# NBM.net
KiCad netlist of a schematic drawn in Altium Designer
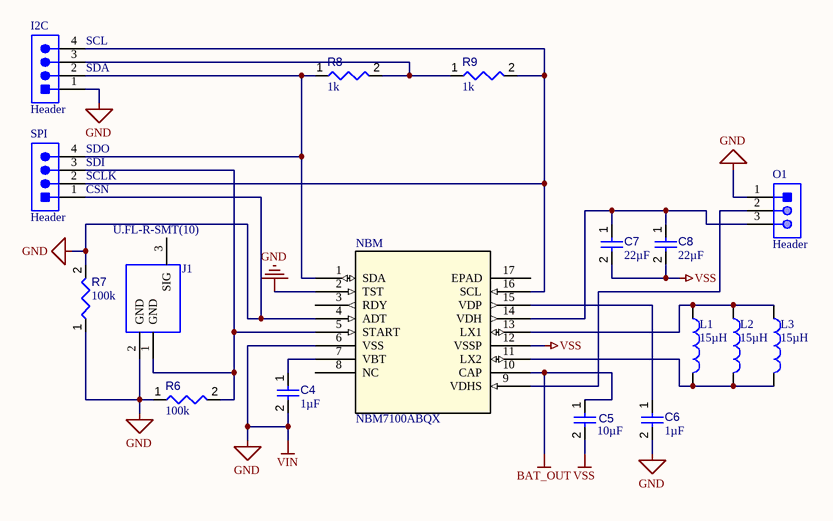
[diagram p0: NBM.SchDoc]

(export (version "E")
  (design (tool "Eeschema 10.0.6"))
  (components
    (comp (ref "C4")
      (value "1µF")
      (footprint "FP-GRM155-0_1-IPC_C")
      (fields (field (name "Comment") "GRM155Z71A105KE01D"))
      (libsource (lib "21520293 21520293") (part "CAP-NP-2"))
    )
    (comp (ref "C5")
      (value "10µF")
      (footprint "FP-GRM155-0_2-IPC_A")
      (fields (field (name "Comment") "GRM155R60J106ME44D"))
      (libsource (lib "21520293 21520293") (part "CAP-NP-2"))
    )
    (comp (ref "C6")
      (value "1µF")
      (footprint "FP-GRM155-0_1-IPC_C")
      (fields (field (name "Comment") "GRM155Z71A105KE01D"))
      (libsource (lib "21520293 21520293") (part "CAP-NP-2"))
    )
    (comp (ref "C7")
      (value "22µF")
      (footprint "FP-GRM158-0_2-MFG")
      (fields (field (name "Comment") "GRM158R61A226ME15D"))
      (libsource (lib "21520293 21520293") (part "CAP-NP-2"))
    )
    (comp (ref "C8")
      (value "22µF")
      (footprint "FP-GRM158-0_2-MFG")
      (fields (field (name "Comment") "GRM158R61A226ME15D"))
      (libsource (lib "21520293 21520293") (part "CAP-NP-2"))
    )
    (comp (ref "I2C")
      (value "Header")
      (footprint "JST-S4B-XH-A(LF)(SN)_V")
      (fields (field (name "MANUFACTURER") "JST"))
      (libsource (lib "21520293 21520293") (part "CN-1P-M-R4"))
    )
    (comp (ref "J1")
      (value "U.FL-R-SMT(10)")
      (footprint "HRS-U.FL-R-SMT_V")
      (fields (field (name "MANUFACTURER") "Hirose Electric"))
      (libsource (lib "21520293 21520293") (part "HRS-U.FL-R-SMT-3"))
    )
    (comp (ref "L1")
      (value "15µH")
      (footprint "FP-MLZ1608-IPC_C")
      (description "General Purpose Inductor, 15uH, 20%, 1 Element, Ferrite-Core, SMD, 0603")
      (fields (field (name "Comment") "MLZ1608N150LTD25"))
      (libsource (lib "21520293 21520293") (part "IND-2"))
    )
    (comp (ref "L2")
      (value "15µH")
      (footprint "FP-MLZ1608-IPC_C")
      (description "General Purpose Inductor, 15uH, 20%, 1 Element, Ferrite-Core, SMD, 0603")
      (fields (field (name "Comment") "MLZ1608N150LTD25"))
      (libsource (lib "21520293 21520293") (part "IND-2"))
    )
    (comp (ref "L3")
      (value "15µH")
      (footprint "FP-MLZ1608-IPC_C")
      (description "General Purpose Inductor, 15uH, 20%, 1 Element, Ferrite-Core, SMD, 0603")
      (fields (field (name "Comment") "MLZ1608N150LTD25"))
      (libsource (lib "21520293 21520293") (part "IND-2"))
    )
    (comp (ref "NBM")
      (value "NBM7100ABQX")
      (footprint "DHVQFN16_NEX")
      (description "No Description Available")
      (fields (field (name "COPYRIGHT") "Copyright (C) 2023 Ultra Librarian. All rights reserved."))
      (libsource (lib "NBM7100ABQX") (part "NBM7100ABQX"))
    )
    (comp (ref "O1")
      (value "Header")
      (footprint "JST-S3B-XH-A(LF)(SN)_V")
      (fields (field (name "MANUFACTURER") "JST"))
      (libsource (lib "21520293 21520293") (part "CN-1P-M-R3"))
    )
    (comp (ref "R6")
      (value "100k")
      (footprint "RESC1005X40X25ML05T05")
      (description "Chip Resistor, 100 KOhm, +/- 1%, 0.063 W, -55 to 155 degC, 0402 (1005 Metric)")
      (fields (field (name "TOLERANCE") "1%") (field (name "POWER") "63mW"))
      (libsource (lib "21520293 21520293") (part "RES-2"))
    )
    (comp (ref "R7")
      (value "100k")
      (footprint "RESC1005X40X25ML05T05")
      (description "Chip Resistor, 100 KOhm, +/- 1%, 0.063 W, -55 to 155 degC, 0402 (1005 Metric)")
      (fields (field (name "TOLERANCE") "1%") (field (name "POWER") "63mW"))
      (libsource (lib "21520293 21520293") (part "RES-2"))
    )
    (comp (ref "R8")
      (value "1k")
      (footprint "RESC1005X40X25ML10T10")
      (description "Chip Resistor, 1 KOhm, +/- 5%, 0.063 W, -55 to 155 degC, 0402 (1005 Metric)")
      (fields (field (name "TOLERANCE") "5%") (field (name "POWER") "63mW"))
      (libsource (lib "21520293 21520293") (part "RES-2"))
    )
    (comp (ref "R9")
      (value "1k")
      (footprint "RESC1005X40X25ML10T10")
      (description "Chip Resistor, 1 KOhm, +/- 5%, 0.063 W, -55 to 155 degC, 0402 (1005 Metric)")
      (fields (field (name "TOLERANCE") "5%") (field (name "POWER") "63mW"))
      (libsource (lib "21520293 21520293") (part "RES-2"))
    )
    (comp (ref "SPI")
      (value "Header")
      (footprint "JST-S4B-XH-A(LF)(SN)_V")
      (fields (field (name "MANUFACTURER") "JST"))
      (libsource (lib "21520293 21520293") (part "CN-1P-M-R4"))
    )
  )
  (nets
    (net (code "1") (name "BAT_OUT") (class "Default")
      (node (ref "C5") (pin "1") (pinfunction "1_1") (pintype "passive"))
      (node (ref "NBM") (pin "10") (pinfunction "CAP_10") (pintype "power_in"))
    )
    (net (code "2") (name "GND") (class "Default")
      (node (ref "C4") (pin "2") (pinfunction "2_2") (pintype "passive"))
      (node (ref "C6") (pin "2") (pinfunction "2_2") (pintype "passive"))
      (node (ref "I2C") (pin "1") (pinfunction "1_1") (pintype "passive"))
      (node (ref "J1") (pin "2") (pinfunction "GND_2") (pintype "power_in"))
      (node (ref "NBM") (pin "2") (pinfunction "TST_2") (pintype "input"))
      (node (ref "NBM") (pin "4") (pinfunction "ADT_4") (pintype "input"))
      (node (ref "NBM") (pin "6") (pinfunction "VSS_6") (pintype "power_in"))
      (node (ref "O1") (pin "1") (pinfunction "1_1") (pintype "passive"))
      (node (ref "R6") (pin "1") (pinfunction "1_1") (pintype "passive"))
      (node (ref "R7") (pin "1") (pinfunction "1_1") (pintype "passive"))
      (node (ref "R7") (pin "2") (pinfunction "2_2") (pintype "passive"))
      (node (ref "SPI") (pin "1") (pinfunction "1_1") (pintype "passive"))
    )
    (net (code "3") (name "Net-(I2C-Pad3)") (class "Default")
      (node (ref "I2C") (pin "3") (pinfunction "3_3") (pintype "passive"))
      (node (ref "R8") (pin "2") (pinfunction "2_2") (pintype "passive"))
      (node (ref "R9") (pin "1") (pinfunction "1_1") (pintype "passive"))
    )
    (net (code "4") (name "Net-(NBM-LX1)") (class "Default")
      (node (ref "L1") (pin "1") (pinfunction "1_1") (pintype "passive"))
      (node (ref "L2") (pin "1") (pinfunction "1_1") (pintype "passive"))
      (node (ref "L3") (pin "1") (pinfunction "1_1") (pintype "passive"))
      (node (ref "NBM") (pin "13") (pinfunction "LX1_13") (pintype "bidirectional"))
    )
    (net (code "5") (name "Net-(NBM-LX2)") (class "Default")
      (node (ref "L1") (pin "2") (pinfunction "2_2") (pintype "passive"))
      (node (ref "L2") (pin "2") (pinfunction "2_2") (pintype "passive"))
      (node (ref "L3") (pin "2") (pinfunction "2_2") (pintype "passive"))
      (node (ref "NBM") (pin "11") (pinfunction "LX2_11") (pintype "bidirectional"))
    )
    (net (code "6") (name "Net-(NBM-SCL)") (class "Default")
      (node (ref "I2C") (pin "4") (pinfunction "4_4") (pintype "passive"))
      (node (ref "NBM") (pin "16") (pinfunction "SCL_16") (pintype "input"))
      (node (ref "R9") (pin "2") (pinfunction "2_2") (pintype "passive"))
      (node (ref "SPI") (pin "2") (pinfunction "2_2") (pintype "passive"))
    )
    (net (code "7") (name "Net-(NBM-SDA)") (class "Default")
      (node (ref "I2C") (pin "2") (pinfunction "2_2") (pintype "passive"))
      (node (ref "NBM") (pin "1") (pinfunction "SDA_1") (pintype "bidirectional"))
      (node (ref "R8") (pin "1") (pinfunction "1_1") (pintype "passive"))
      (node (ref "SPI") (pin "4") (pinfunction "4_4") (pintype "passive"))
    )
    (net (code "8") (name "Net-(NBM-START)") (class "Default")
      (node (ref "J1") (pin "1") (pinfunction "GND_1") (pintype "power_in"))
      (node (ref "NBM") (pin "5") (pinfunction "START_5") (pintype "input"))
      (node (ref "R6") (pin "2") (pinfunction "2_2") (pintype "passive"))
      (node (ref "SPI") (pin "3") (pinfunction "3_3") (pintype "passive"))
    )
    (net (code "9") (name "Net-(NBM-VBT)") (class "Default")
      (node (ref "C4") (pin "1") (pinfunction "1_1") (pintype "passive"))
      (node (ref "NBM") (pin "7") (pinfunction "VBT_7") (pintype "power_in"))
    )
    (net (code "10") (name "Net-(NBM-VDH)") (class "Default")
      (node (ref "C7") (pin "1") (pinfunction "1_1") (pintype "passive"))
      (node (ref "C8") (pin "1") (pinfunction "1_1") (pintype "passive"))
      (node (ref "NBM") (pin "14") (pinfunction "VDH_14") (pintype "output"))
      (node (ref "O1") (pin "3") (pinfunction "3_3") (pintype "passive"))
    )
    (net (code "11") (name "Net-(NBM-VDHS)") (class "Default")
      (node (ref "NBM") (pin "9") (pinfunction "VDHS_9") (pintype "input"))
      (node (ref "O1") (pin "2") (pinfunction "2_2") (pintype "passive"))
    )
    (net (code "12") (name "Net-(NBM-VDP)") (class "Default")
      (node (ref "C6") (pin "1") (pinfunction "1_1") (pintype "passive"))
      (node (ref "NBM") (pin "15") (pinfunction "VDP_15") (pintype "output"))
    )
    (net (code "13") (name "VSS") (class "Default")
      (node (ref "C5") (pin "2") (pinfunction "2_2") (pintype "passive"))
      (node (ref "C7") (pin "2") (pinfunction "2_2") (pintype "passive"))
      (node (ref "C8") (pin "2") (pinfunction "2_2") (pintype "passive"))
      (node (ref "NBM") (pin "12") (pinfunction "VSSP_12") (pintype "power_in"))
    )
    (net (code "14") (name "unconnected-(J1-SIG-Pad3)") (class "Default")
      (node (ref "J1") (pin "3") (pinfunction "SIG_3") (pintype "passive"))
    )
    (net (code "15") (name "unconnected-(NBM-EPAD-Pad17)") (class "Default")
      (node (ref "NBM") (pin "17") (pinfunction "EPAD_17") (pintype "power_in"))
    )
    (net (code "16") (name "unconnected-(NBM-NC-Pad8)") (class "Default")
      (node (ref "NBM") (pin "8") (pinfunction "NC_8") (pintype "passive"))
    )
    (net (code "17") (name "unconnected-(NBM-RDY-Pad3)") (class "Default")
      (node (ref "NBM") (pin "3") (pinfunction "RDY_3") (pintype "output"))
    )
  )
)
